# 780-00012-P2_Sch_M2_Focus_Drive_old.net
KiCad netlist of a schematic drawn in Altium Designer
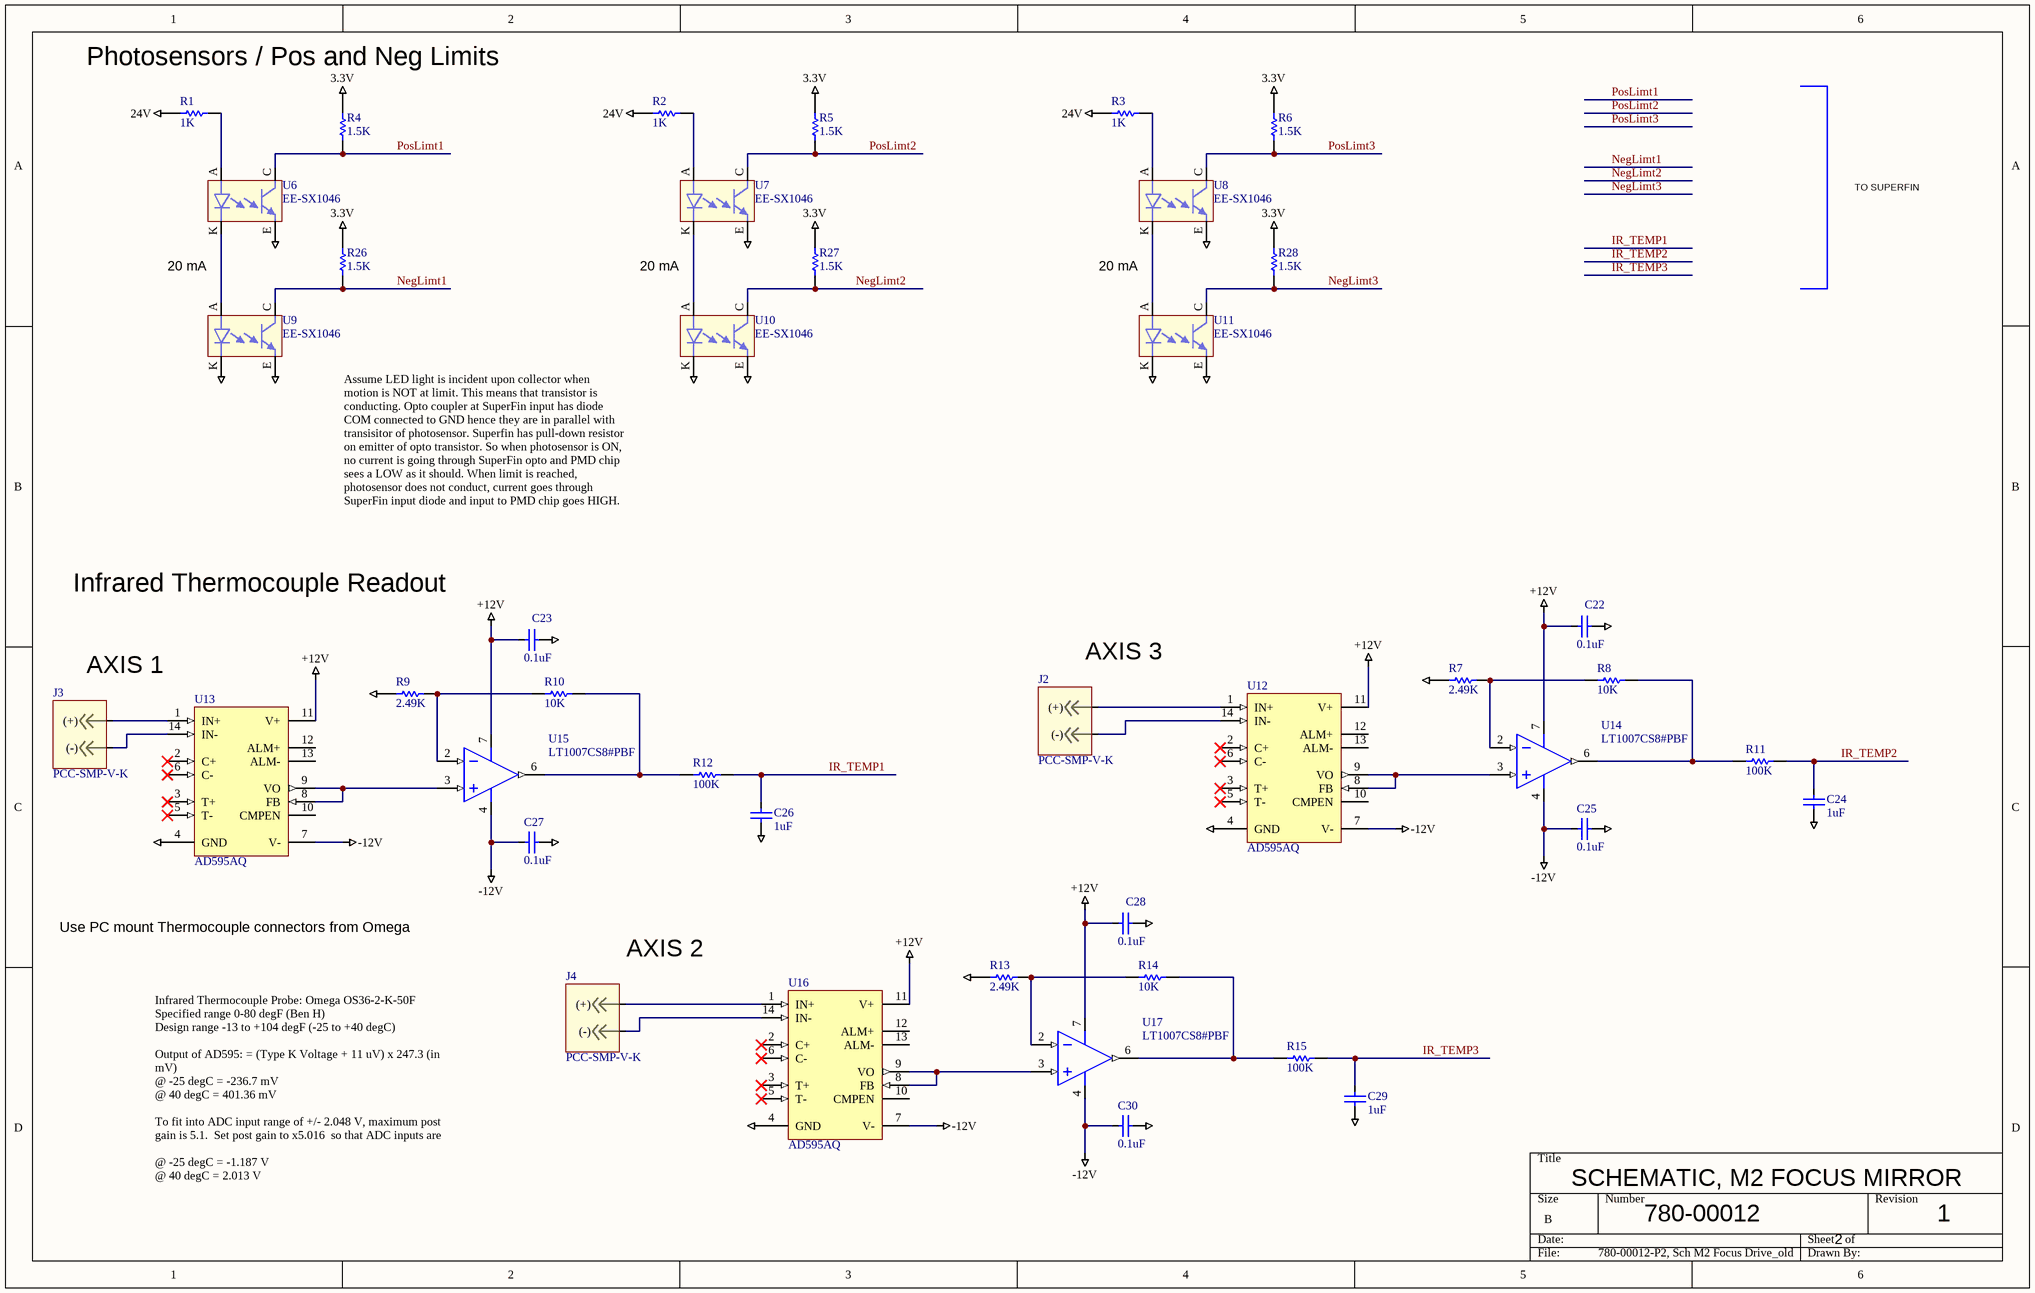
[diagram p0: 780-00012-P2, Sch M2 Focus Drive_old.SchDoc]

(export (version "E")
  (design (tool "Eeschema 10.0.6"))
  (components
    (comp (ref "C22")
      (value "0.1uF")
      (footprint "SMD_0805")
      (description "Capacitor")
      (fields (field (name "Comment") "Cap SMD"))
      (libsource (lib "Richs Schematic Components") (part "Cap SMD"))
    )
    (comp (ref "C23")
      (value "0.1uF")
      (footprint "SMD_0805")
      (description "Capacitor")
      (fields (field (name "Comment") "Cap SMD"))
      (libsource (lib "Richs Schematic Components") (part "Cap SMD"))
    )
    (comp (ref "C24")
      (value "1uF")
      (footprint "SMD_0805")
      (description "Capacitor")
      (fields (field (name "Comment") "Cap SMD"))
      (libsource (lib "Richs Schematic Components") (part "Cap SMD"))
    )
    (comp (ref "C25")
      (value "0.1uF")
      (footprint "SMD_0805")
      (description "Capacitor")
      (fields (field (name "Comment") "Cap SMD"))
      (libsource (lib "Richs Schematic Components") (part "Cap SMD"))
    )
    (comp (ref "C26")
      (value "1uF")
      (footprint "SMD_0805")
      (description "Capacitor")
      (fields (field (name "Comment") "Cap SMD"))
      (libsource (lib "Richs Schematic Components") (part "Cap SMD"))
    )
    (comp (ref "C27")
      (value "0.1uF")
      (footprint "SMD_0805")
      (description "Capacitor")
      (fields (field (name "Comment") "Cap SMD"))
      (libsource (lib "Richs Schematic Components") (part "Cap SMD"))
    )
    (comp (ref "C28")
      (value "0.1uF")
      (footprint "SMD_0805")
      (description "Capacitor")
      (fields (field (name "Comment") "Cap SMD"))
      (libsource (lib "Richs Schematic Components") (part "Cap SMD"))
    )
    (comp (ref "C29")
      (value "1uF")
      (footprint "SMD_0805")
      (description "Capacitor")
      (fields (field (name "Comment") "Cap SMD"))
      (libsource (lib "Richs Schematic Components") (part "Cap SMD"))
    )
    (comp (ref "C30")
      (value "0.1uF")
      (footprint "SMD_0805")
      (description "Capacitor")
      (fields (field (name "Comment") "Cap SMD"))
      (libsource (lib "Richs Schematic Components") (part "Cap SMD"))
    )
    (comp (ref "J2")
      (value "PCC-SMP-V-K")
      (footprint "THERMOCOUPLE")
      (description "T/C Conn PCB mount vertical")
      (libsource (lib "Richs Schematic Components") (part "Thermocouple Connector"))
    )
    (comp (ref "J3")
      (value "PCC-SMP-V-K")
      (footprint "THERMOCOUPLE")
      (description "T/C Conn PCB mount vertical")
      (libsource (lib "Richs Schematic Components") (part "Thermocouple Connector"))
    )
    (comp (ref "J4")
      (value "PCC-SMP-V-K")
      (footprint "THERMOCOUPLE")
      (description "T/C Conn PCB mount vertical")
      (libsource (lib "Richs Schematic Components") (part "Thermocouple Connector"))
    )
    (comp (ref "R1")
      (value "1K")
      (footprint "SMD_0805")
      (description "Resistor 0805")
      (fields (field (name "MANUFACTURER") "Vishay/Dale") (field (name "Comment") "Res 0805"))
      (libsource (lib "Richs Schematic Components") (part "Res SMD"))
    )
    (comp (ref "R2")
      (value "1K")
      (footprint "SMD_0805")
      (description "Resistor 0805")
      (fields (field (name "MANUFACTURER") "Vishay/Dale") (field (name "Comment") "Res 0805"))
      (libsource (lib "Richs Schematic Components") (part "Res SMD"))
    )
    (comp (ref "R3")
      (value "1K")
      (footprint "SMD_0805")
      (description "Resistor 0805")
      (fields (field (name "MANUFACTURER") "Vishay/Dale") (field (name "Comment") "Res 0805"))
      (libsource (lib "Richs Schematic Components") (part "Res SMD"))
    )
    (comp (ref "R4")
      (value "1.5K")
      (footprint "SMD_0805")
      (description "Resistor 0805")
      (fields (field (name "MANUFACTURER") "Vishay/Dale") (field (name "Comment") "Res 0805"))
      (libsource (lib "Richs Schematic Components") (part "Res SMD"))
    )
    (comp (ref "R5")
      (value "1.5K")
      (footprint "SMD_0805")
      (description "Resistor 0805")
      (fields (field (name "MANUFACTURER") "Vishay/Dale") (field (name "Comment") "Res 0805"))
      (libsource (lib "Richs Schematic Components") (part "Res SMD"))
    )
    (comp (ref "R6")
      (value "1.5K")
      (footprint "SMD_0805")
      (description "Resistor 0805")
      (fields (field (name "MANUFACTURER") "Vishay/Dale") (field (name "Comment") "Res 0805"))
      (libsource (lib "Richs Schematic Components") (part "Res SMD"))
    )
    (comp (ref "R7")
      (value "2.49K")
      (footprint "SMD_0805")
      (description "Resistor 0805")
      (fields (field (name "MANUFACTURER") "Vishay/Dale") (field (name "Comment") "Res 0805"))
      (libsource (lib "Richs Schematic Components") (part "Res SMD"))
    )
    (comp (ref "R8")
      (value "10K")
      (footprint "SMD_0805")
      (description "Resistor 0805")
      (fields (field (name "MANUFACTURER") "Vishay/Dale") (field (name "Comment") "Res 0805"))
      (libsource (lib "Richs Schematic Components") (part "Res SMD"))
    )
    (comp (ref "R9")
      (value "2.49K")
      (footprint "SMD_0805")
      (description "Resistor 0805")
      (fields (field (name "MANUFACTURER") "Vishay/Dale") (field (name "Comment") "Res 0805"))
      (libsource (lib "Richs Schematic Components") (part "Res SMD"))
    )
    (comp (ref "R10")
      (value "10K")
      (footprint "SMD_0805")
      (description "Resistor 0805")
      (fields (field (name "MANUFACTURER") "Vishay/Dale") (field (name "Comment") "Res 0805"))
      (libsource (lib "Richs Schematic Components") (part "Res SMD"))
    )
    (comp (ref "R11")
      (value "100K")
      (footprint "SMD_0805")
      (description "Resistor 0805")
      (fields (field (name "MANUFACTURER") "Vishay/Dale") (field (name "Comment") "Res 0805"))
      (libsource (lib "Richs Schematic Components") (part "Res SMD"))
    )
    (comp (ref "R12")
      (value "100K")
      (footprint "SMD_0805")
      (description "Resistor 0805")
      (fields (field (name "MANUFACTURER") "Vishay/Dale") (field (name "Comment") "Res 0805"))
      (libsource (lib "Richs Schematic Components") (part "Res SMD"))
    )
    (comp (ref "R13")
      (value "2.49K")
      (footprint "SMD_0805")
      (description "Resistor 0805")
      (fields (field (name "MANUFACTURER") "Vishay/Dale") (field (name "Comment") "Res 0805"))
      (libsource (lib "Richs Schematic Components") (part "Res SMD"))
    )
    (comp (ref "R14")
      (value "10K")
      (footprint "SMD_0805")
      (description "Resistor 0805")
      (fields (field (name "MANUFACTURER") "Vishay/Dale") (field (name "Comment") "Res 0805"))
      (libsource (lib "Richs Schematic Components") (part "Res SMD"))
    )
    (comp (ref "R15")
      (value "100K")
      (footprint "SMD_0805")
      (description "Resistor 0805")
      (fields (field (name "MANUFACTURER") "Vishay/Dale") (field (name "Comment") "Res 0805"))
      (libsource (lib "Richs Schematic Components") (part "Res SMD"))
    )
    (comp (ref "R26")
      (value "1.5K")
      (footprint "SMD_0805")
      (description "Resistor 0805")
      (fields (field (name "MANUFACTURER") "Vishay/Dale") (field (name "Comment") "Res 0805"))
      (libsource (lib "Richs Schematic Components") (part "Res SMD"))
    )
    (comp (ref "R27")
      (value "1.5K")
      (footprint "SMD_0805")
      (description "Resistor 0805")
      (fields (field (name "MANUFACTURER") "Vishay/Dale") (field (name "Comment") "Res 0805"))
      (libsource (lib "Richs Schematic Components") (part "Res SMD"))
    )
    (comp (ref "R28")
      (value "1.5K")
      (footprint "SMD_0805")
      (description "Resistor 0805")
      (fields (field (name "MANUFACTURER") "Vishay/Dale") (field (name "Comment") "Res 0805"))
      (libsource (lib "Richs Schematic Components") (part "Res SMD"))
    )
    (comp (ref "U6")
      (value "EE-SX1046")
      (footprint "Photo-sensor")
      (description "Omron EE-SX1046")
      (libsource (lib "Richs Schematic Components") (part "Photo-sensor"))
    )
    (comp (ref "U7")
      (value "EE-SX1046")
      (footprint "Photo-sensor")
      (description "Omron EE-SX1046")
      (libsource (lib "Richs Schematic Components") (part "Photo-sensor"))
    )
    (comp (ref "U8")
      (value "EE-SX1046")
      (footprint "Photo-sensor")
      (description "Omron EE-SX1046")
      (libsource (lib "Richs Schematic Components") (part "Photo-sensor"))
    )
    (comp (ref "U9")
      (value "EE-SX1046")
      (footprint "Photo-sensor")
      (description "Omron EE-SX1046")
      (libsource (lib "Richs Schematic Components") (part "Photo-sensor"))
    )
    (comp (ref "U10")
      (value "EE-SX1046")
      (footprint "Photo-sensor")
      (description "Omron EE-SX1046")
      (libsource (lib "Richs Schematic Components") (part "Photo-sensor"))
    )
    (comp (ref "U11")
      (value "EE-SX1046")
      (footprint "Photo-sensor")
      (description "Omron EE-SX1046")
      (libsource (lib "Richs Schematic Components") (part "Photo-sensor"))
    )
    (comp (ref "U12")
      (value "AD595AQ")
      (footprint "Q-14_A")
      (description "Monolithic Thermocouple Amplifier with Cold Junction Compensation")
      (fields (field (name "PUBLISHER") "Altium Limited"))
      (libsource (lib "AD Thermocouple Amplifier") (part "AD595AQ"))
    )
    (comp (ref "U13")
      (value "AD595AQ")
      (footprint "Q-14_A")
      (description "Monolithic Thermocouple Amplifier with Cold Junction Compensation")
      (fields (field (name "PUBLISHER") "Altium Limited"))
      (libsource (lib "AD Thermocouple Amplifier") (part "AD595AQ"))
    )
    (comp (ref "U14")
      (value "LT1007CS8#PBF")
      (footprint "S8_M")
      (description "Low Noise BJT input opamp")
      (fields (field (name "MANUFACTURER") "Linear Tech"))
      (libsource (lib "Richs Schematic Components") (part "LT1007CS8#PBF"))
    )
    (comp (ref "U15")
      (value "LT1007CS8#PBF")
      (footprint "S8_M")
      (description "Low Noise BJT input opamp")
      (fields (field (name "MANUFACTURER") "Linear Tech"))
      (libsource (lib "Richs Schematic Components") (part "LT1007CS8#PBF"))
    )
    (comp (ref "U16")
      (value "AD595AQ")
      (footprint "Q-14_A")
      (description "Monolithic Thermocouple Amplifier with Cold Junction Compensation")
      (fields (field (name "PUBLISHER") "Altium Limited"))
      (libsource (lib "AD Thermocouple Amplifier") (part "AD595AQ"))
    )
    (comp (ref "U17")
      (value "LT1007CS8#PBF")
      (footprint "S8_M")
      (description "Low Noise BJT input opamp")
      (fields (field (name "MANUFACTURER") "Linear Tech"))
      (libsource (lib "Richs Schematic Components") (part "LT1007CS8#PBF"))
    )
  )
  (nets
    (net (code "1") (name "+12V") (class "Default")
      (node (ref "C22") (pin "2") (pinfunction "2_2") (pintype "passive"))
      (node (ref "C23") (pin "2") (pinfunction "2_2") (pintype "passive"))
      (node (ref "C28") (pin "2") (pinfunction "2_2") (pintype "passive"))
      (node (ref "U12") (pin "11") (pinfunction "V+_11") (pintype "power_in"))
      (node (ref "U13") (pin "11") (pinfunction "V+_11") (pintype "power_in"))
      (node (ref "U14") (pin "7") (pinfunction "V+_7") (pintype "power_in"))
      (node (ref "U15") (pin "7") (pinfunction "V+_7") (pintype "power_in"))
      (node (ref "U16") (pin "11") (pinfunction "V+_11") (pintype "power_in"))
      (node (ref "U17") (pin "7") (pinfunction "V+_7") (pintype "power_in"))
    )
    (net (code "2") (name "-12V") (class "Default")
      (node (ref "C25") (pin "2") (pinfunction "2_2") (pintype "passive"))
      (node (ref "C27") (pin "2") (pinfunction "2_2") (pintype "passive"))
      (node (ref "C30") (pin "2") (pinfunction "2_2") (pintype "passive"))
      (node (ref "U12") (pin "7") (pinfunction "V-_7") (pintype "power_in"))
      (node (ref "U13") (pin "7") (pinfunction "V-_7") (pintype "power_in"))
      (node (ref "U14") (pin "4") (pinfunction "V-_4") (pintype "power_in"))
      (node (ref "U15") (pin "4") (pinfunction "V-_4") (pintype "power_in"))
      (node (ref "U16") (pin "7") (pinfunction "V-_7") (pintype "power_in"))
      (node (ref "U17") (pin "4") (pinfunction "V-_4") (pintype "power_in"))
    )
    (net (code "3") (name "/IR_TEMP1") (class "Default")
      (node (ref "C26") (pin "2") (pinfunction "2_2") (pintype "passive"))
      (node (ref "R12") (pin "2") (pinfunction "2_2") (pintype "passive"))
    )
    (net (code "4") (name "/IR_TEMP2") (class "Default")
      (node (ref "C24") (pin "2") (pinfunction "2_2") (pintype "passive"))
      (node (ref "R11") (pin "2") (pinfunction "2_2") (pintype "passive"))
    )
    (net (code "5") (name "/IR_TEMP3") (class "Default")
      (node (ref "C29") (pin "2") (pinfunction "2_2") (pintype "passive"))
      (node (ref "R15") (pin "2") (pinfunction "2_2") (pintype "passive"))
    )
    (net (code "6") (name "/NegLimt1") (class "Default")
      (node (ref "R26") (pin "1") (pinfunction "1_1") (pintype "passive"))
      (node (ref "U9") (pin "C") (pinfunction "collector_C") (pintype "passive"))
    )
    (net (code "7") (name "/NegLimt2") (class "Default")
      (node (ref "R27") (pin "1") (pinfunction "1_1") (pintype "passive"))
      (node (ref "U10") (pin "C") (pinfunction "collector_C") (pintype "passive"))
    )
    (net (code "8") (name "/NegLimt3") (class "Default")
      (node (ref "R28") (pin "1") (pinfunction "1_1") (pintype "passive"))
      (node (ref "U11") (pin "C") (pinfunction "collector_C") (pintype "passive"))
    )
    (net (code "9") (name "/PosLimt1") (class "Default")
      (node (ref "R4") (pin "1") (pinfunction "1_1") (pintype "passive"))
      (node (ref "U6") (pin "C") (pinfunction "collector_C") (pintype "passive"))
    )
    (net (code "10") (name "/PosLimt2") (class "Default")
      (node (ref "R5") (pin "1") (pinfunction "1_1") (pintype "passive"))
      (node (ref "U7") (pin "C") (pinfunction "collector_C") (pintype "passive"))
    )
    (net (code "11") (name "/PosLimt3") (class "Default")
      (node (ref "R6") (pin "1") (pinfunction "1_1") (pintype "passive"))
      (node (ref "U8") (pin "C") (pinfunction "collector_C") (pintype "passive"))
    )
    (net (code "12") (name "3.3V") (class "Default")
      (node (ref "R26") (pin "2") (pinfunction "2_2") (pintype "passive"))
      (node (ref "R27") (pin "2") (pinfunction "2_2") (pintype "passive"))
      (node (ref "R28") (pin "2") (pinfunction "2_2") (pintype "passive"))
      (node (ref "R4") (pin "2") (pinfunction "2_2") (pintype "passive"))
      (node (ref "R5") (pin "2") (pinfunction "2_2") (pintype "passive"))
      (node (ref "R6") (pin "2") (pinfunction "2_2") (pintype "passive"))
    )
    (net (code "13") (name "24V") (class "Default")
      (node (ref "R1") (pin "2") (pinfunction "2_2") (pintype "passive"))
      (node (ref "R2") (pin "2") (pinfunction "2_2") (pintype "passive"))
      (node (ref "R3") (pin "2") (pinfunction "2_2") (pintype "passive"))
    )
    (net (code "14") (name "GND") (class "Default")
      (node (ref "C22") (pin "1") (pinfunction "1_1") (pintype "passive"))
      (node (ref "C23") (pin "1") (pinfunction "1_1") (pintype "passive"))
      (node (ref "C24") (pin "1") (pinfunction "1_1") (pintype "passive"))
      (node (ref "C25") (pin "1") (pinfunction "1_1") (pintype "passive"))
      (node (ref "C26") (pin "1") (pinfunction "1_1") (pintype "passive"))
      (node (ref "C27") (pin "1") (pinfunction "1_1") (pintype "passive"))
      (node (ref "C28") (pin "1") (pinfunction "1_1") (pintype "passive"))
      (node (ref "C29") (pin "1") (pinfunction "1_1") (pintype "passive"))
      (node (ref "C30") (pin "1") (pinfunction "1_1") (pintype "passive"))
      (node (ref "R13") (pin "1") (pinfunction "1_1") (pintype "passive"))
      (node (ref "R7") (pin "1") (pinfunction "1_1") (pintype "passive"))
      (node (ref "R9") (pin "1") (pinfunction "1_1") (pintype "passive"))
      (node (ref "U10") (pin "E") (pinfunction "emitter_E") (pintype "passive"))
      (node (ref "U10") (pin "K") (pinfunction "cathode_K") (pintype "passive"))
      (node (ref "U11") (pin "E") (pinfunction "emitter_E") (pintype "passive"))
      (node (ref "U11") (pin "K") (pinfunction "cathode_K") (pintype "passive"))
      (node (ref "U12") (pin "4") (pinfunction "GND_4") (pintype "power_in"))
      (node (ref "U13") (pin "4") (pinfunction "GND_4") (pintype "power_in"))
      (node (ref "U16") (pin "4") (pinfunction "GND_4") (pintype "power_in"))
      (node (ref "U6") (pin "E") (pinfunction "emitter_E") (pintype "passive"))
      (node (ref "U7") (pin "E") (pinfunction "emitter_E") (pintype "passive"))
      (node (ref "U8") (pin "E") (pinfunction "emitter_E") (pintype "passive"))
      (node (ref "U9") (pin "E") (pinfunction "emitter_E") (pintype "passive"))
      (node (ref "U9") (pin "K") (pinfunction "cathode_K") (pintype "passive"))
    )
    (net (code "15") (name "Net-(J2-(+))") (class "Default")
      (node (ref "J2") (pin "1") (pinfunction "(+)_1") (pintype "passive"))
      (node (ref "U12") (pin "1") (pinfunction "IN+_1") (pintype "input"))
    )
    (net (code "16") (name "Net-(J2-(-))") (class "Default")
      (node (ref "J2") (pin "2") (pinfunction "(-)_2") (pintype "passive"))
      (node (ref "U12") (pin "14") (pinfunction "IN-_14") (pintype "input"))
    )
    (net (code "17") (name "Net-(J3-(+))") (class "Default")
      (node (ref "J3") (pin "1") (pinfunction "(+)_1") (pintype "passive"))
      (node (ref "U13") (pin "1") (pinfunction "IN+_1") (pintype "input"))
    )
    (net (code "18") (name "Net-(J3-(-))") (class "Default")
      (node (ref "J3") (pin "2") (pinfunction "(-)_2") (pintype "passive"))
      (node (ref "U13") (pin "14") (pinfunction "IN-_14") (pintype "input"))
    )
    (net (code "19") (name "Net-(J4-(+))") (class "Default")
      (node (ref "J4") (pin "1") (pinfunction "(+)_1") (pintype "passive"))
      (node (ref "U16") (pin "1") (pinfunction "IN+_1") (pintype "input"))
    )
    (net (code "20") (name "Net-(J4-(-))") (class "Default")
      (node (ref "J4") (pin "2") (pinfunction "(-)_2") (pintype "passive"))
      (node (ref "U16") (pin "14") (pinfunction "IN-_14") (pintype "input"))
    )
    (net (code "21") (name "Net-(U6-anode)") (class "Default")
      (node (ref "R1") (pin "1") (pinfunction "1_1") (pintype "passive"))
      (node (ref "U6") (pin "A") (pinfunction "anode_A") (pintype "passive"))
    )
    (net (code "22") (name "Net-(U6-cathode)") (class "Default")
      (node (ref "U6") (pin "K") (pinfunction "cathode_K") (pintype "passive"))
      (node (ref "U9") (pin "A") (pinfunction "anode_A") (pintype "passive"))
    )
    (net (code "23") (name "Net-(U7-anode)") (class "Default")
      (node (ref "R2") (pin "1") (pinfunction "1_1") (pintype "passive"))
      (node (ref "U7") (pin "A") (pinfunction "anode_A") (pintype "passive"))
    )
    (net (code "24") (name "Net-(U8-anode)") (class "Default")
      (node (ref "R3") (pin "1") (pinfunction "1_1") (pintype "passive"))
      (node (ref "U8") (pin "A") (pinfunction "anode_A") (pintype "passive"))
    )
    (net (code "25") (name "Net-(U10-anode)") (class "Default")
      (node (ref "U10") (pin "A") (pinfunction "anode_A") (pintype "passive"))
      (node (ref "U7") (pin "K") (pinfunction "cathode_K") (pintype "passive"))
    )
    (net (code "26") (name "Net-(U11-anode)") (class "Default")
      (node (ref "U11") (pin "A") (pinfunction "anode_A") (pintype "passive"))
      (node (ref "U8") (pin "K") (pinfunction "cathode_K") (pintype "passive"))
    )
    (net (code "27") (name "Net-(U12-FB)") (class "Default")
      (node (ref "U12") (pin "8") (pinfunction "FB_8") (pintype "input"))
      (node (ref "U12") (pin "9") (pinfunction "VO_9") (pintype "output"))
      (node (ref "U14") (pin "3") (pinfunction "IN+_3") (pintype "input"))
    )
    (net (code "28") (name "Net-(U13-FB)") (class "Default")
      (node (ref "U13") (pin "8") (pinfunction "FB_8") (pintype "input"))
      (node (ref "U13") (pin "9") (pinfunction "VO_9") (pintype "output"))
      (node (ref "U15") (pin "3") (pinfunction "IN+_3") (pintype "input"))
    )
    (net (code "29") (name "Net-(U14-IN-)") (class "Default")
      (node (ref "R7") (pin "2") (pinfunction "2_2") (pintype "passive"))
      (node (ref "R8") (pin "1") (pinfunction "1_1") (pintype "passive"))
      (node (ref "U14") (pin "2") (pinfunction "IN-_2") (pintype "input"))
    )
    (net (code "30") (name "Net-(U14-OUT)") (class "Default")
      (node (ref "R11") (pin "1") (pinfunction "1_1") (pintype "passive"))
      (node (ref "R8") (pin "2") (pinfunction "2_2") (pintype "passive"))
      (node (ref "U14") (pin "6") (pinfunction "OUT_6") (pintype "output"))
    )
    (net (code "31") (name "Net-(U15-IN-)") (class "Default")
      (node (ref "R10") (pin "1") (pinfunction "1_1") (pintype "passive"))
      (node (ref "R9") (pin "2") (pinfunction "2_2") (pintype "passive"))
      (node (ref "U15") (pin "2") (pinfunction "IN-_2") (pintype "input"))
    )
    (net (code "32") (name "Net-(U15-OUT)") (class "Default")
      (node (ref "R10") (pin "2") (pinfunction "2_2") (pintype "passive"))
      (node (ref "R12") (pin "1") (pinfunction "1_1") (pintype "passive"))
      (node (ref "U15") (pin "6") (pinfunction "OUT_6") (pintype "output"))
    )
    (net (code "33") (name "Net-(U16-FB)") (class "Default")
      (node (ref "U16") (pin "8") (pinfunction "FB_8") (pintype "input"))
      (node (ref "U16") (pin "9") (pinfunction "VO_9") (pintype "output"))
      (node (ref "U17") (pin "3") (pinfunction "IN+_3") (pintype "input"))
    )
    (net (code "34") (name "Net-(U17-IN-)") (class "Default")
      (node (ref "R13") (pin "2") (pinfunction "2_2") (pintype "passive"))
      (node (ref "R14") (pin "1") (pinfunction "1_1") (pintype "passive"))
      (node (ref "U17") (pin "2") (pinfunction "IN-_2") (pintype "input"))
    )
    (net (code "35") (name "Net-(U17-OUT)") (class "Default")
      (node (ref "R14") (pin "2") (pinfunction "2_2") (pintype "passive"))
      (node (ref "R15") (pin "1") (pinfunction "1_1") (pintype "passive"))
      (node (ref "U17") (pin "6") (pinfunction "OUT_6") (pintype "output"))
    )
    (net (code "36") (name "unconnected-(U12-ALM+-Pad12)") (class "Default")
      (node (ref "U12") (pin "12") (pinfunction "ALM+_12") (pintype "passive"))
    )
    (net (code "37") (name "unconnected-(U12-ALM--Pad13)") (class "Default")
      (node (ref "U12") (pin "13") (pinfunction "ALM-_13") (pintype "passive"))
    )
    (net (code "38") (name "unconnected-(U12-C+-Pad2)") (class "Default")
      (node (ref "U12") (pin "2") (pinfunction "C+_2") (pintype "input+no_connect"))
    )
    (net (code "39") (name "unconnected-(U12-C--Pad6)") (class "Default")
      (node (ref "U12") (pin "6") (pinfunction "C-_6") (pintype "input+no_connect"))
    )
    (net (code "40") (name "unconnected-(U12-CMPEN-Pad10)") (class "Default")
      (node (ref "U12") (pin "10") (pinfunction "CMPEN_10") (pintype "passive"))
    )
    (net (code "41") (name "unconnected-(U12-T+-Pad3)") (class "Default")
      (node (ref "U12") (pin "3") (pinfunction "T+_3") (pintype "input+no_connect"))
    )
    (net (code "42") (name "unconnected-(U12-T--Pad5)") (class "Default")
      (node (ref "U12") (pin "5") (pinfunction "T-_5") (pintype "input+no_connect"))
    )
    (net (code "43") (name "unconnected-(U13-ALM+-Pad12)") (class "Default")
      (node (ref "U13") (pin "12") (pinfunction "ALM+_12") (pintype "passive"))
    )
    (net (code "44") (name "unconnected-(U13-ALM--Pad13)") (class "Default")
      (node (ref "U13") (pin "13") (pinfunction "ALM-_13") (pintype "passive"))
    )
    (net (code "45") (name "unconnected-(U13-C+-Pad2)") (class "Default")
      (node (ref "U13") (pin "2") (pinfunction "C+_2") (pintype "input+no_connect"))
    )
    (net (code "46") (name "unconnected-(U13-C--Pad6)") (class "Default")
      (node (ref "U13") (pin "6") (pinfunction "C-_6") (pintype "input+no_connect"))
    )
    (net (code "47") (name "unconnected-(U13-CMPEN-Pad10)") (class "Default")
      (node (ref "U13") (pin "10") (pinfunction "CMPEN_10") (pintype "passive"))
    )
    (net (code "48") (name "unconnected-(U13-T+-Pad3)") (class "Default")
      (node (ref "U13") (pin "3") (pinfunction "T+_3") (pintype "input+no_connect"))
    )
    (net (code "49") (name "unconnected-(U13-T--Pad5)") (class "Default")
      (node (ref "U13") (pin "5") (pinfunction "T-_5") (pintype "input+no_connect"))
    )
    (net (code "50") (name "unconnected-(U14-NC-Pad5)") (class "Default")
      (node (ref "U14") (pin "5") (pinfunction "NC_5") (pintype "passive"))
    )
    (net (code "51") (name "unconnected-(U14-VOSTRIM-Pad1)") (class "Default")
      (node (ref "U14") (pin "1") (pinfunction "VOSTRIM_1") (pintype "passive"))
    )
    (net (code "52") (name "unconnected-(U14-VOSTRIM-Pad8)") (class "Default")
      (node (ref "U14") (pin "8") (pinfunction "VOSTRIM_8") (pintype "passive"))
    )
    (net (code "53") (name "unconnected-(U15-NC-Pad5)") (class "Default")
      (node (ref "U15") (pin "5") (pinfunction "NC_5") (pintype "passive"))
    )
    (net (code "54") (name "unconnected-(U15-VOSTRIM-Pad1)") (class "Default")
      (node (ref "U15") (pin "1") (pinfunction "VOSTRIM_1") (pintype "passive"))
    )
    (net (code "55") (name "unconnected-(U15-VOSTRIM-Pad8)") (class "Default")
      (node (ref "U15") (pin "8") (pinfunction "VOSTRIM_8") (pintype "passive"))
    )
    (net (code "56") (name "unconnected-(U16-ALM+-Pad12)") (class "Default")
      (node (ref "U16") (pin "12") (pinfunction "ALM+_12") (pintype "passive"))
    )
    (net (code "57") (name "unconnected-(U16-ALM--Pad13)") (class "Default")
      (node (ref "U16") (pin "13") (pinfunction "ALM-_13") (pintype "passive"))
    )
    (net (code "58") (name "unconnected-(U16-C+-Pad2)") (class "Default")
      (node (ref "U16") (pin "2") (pinfunction "C+_2") (pintype "input+no_connect"))
    )
    (net (code "59") (name "unconnected-(U16-C--Pad6)") (class "Default")
      (node (ref "U16") (pin "6") (pinfunction "C-_6") (pintype "input+no_connect"))
    )
    (net (code "60") (name "unconnected-(U16-CMPEN-Pad10)") (class "Default")
      (node (ref "U16") (pin "10") (pinfunction "CMPEN_10") (pintype "passive"))
    )
    (net (code "61") (name "unconnected-(U16-T+-Pad3)") (class "Default")
      (node (ref "U16") (pin "3") (pinfunction "T+_3") (pintype "input+no_connect"))
    )
    (net (code "62") (name "unconnected-(U16-T--Pad5)") (class "Default")
      (node (ref "U16") (pin "5") (pinfunction "T-_5") (pintype "input+no_connect"))
    )
    (net (code "63") (name "unconnected-(U17-NC-Pad5)") (class "Default")
      (node (ref "U17") (pin "5") (pinfunction "NC_5") (pintype "passive"))
    )
    (net (code "64") (name "unconnected-(U17-VOSTRIM-Pad1)") (class "Default")
      (node (ref "U17") (pin "1") (pinfunction "VOSTRIM_1") (pintype "passive"))
    )
    (net (code "65") (name "unconnected-(U17-VOSTRIM-Pad8)") (class "Default")
      (node (ref "U17") (pin "8") (pinfunction "VOSTRIM_8") (pintype "passive"))
    )
  )
)
